# badge-inner-revA.net
KiCad netlist of a schematic drawn in EAGLE
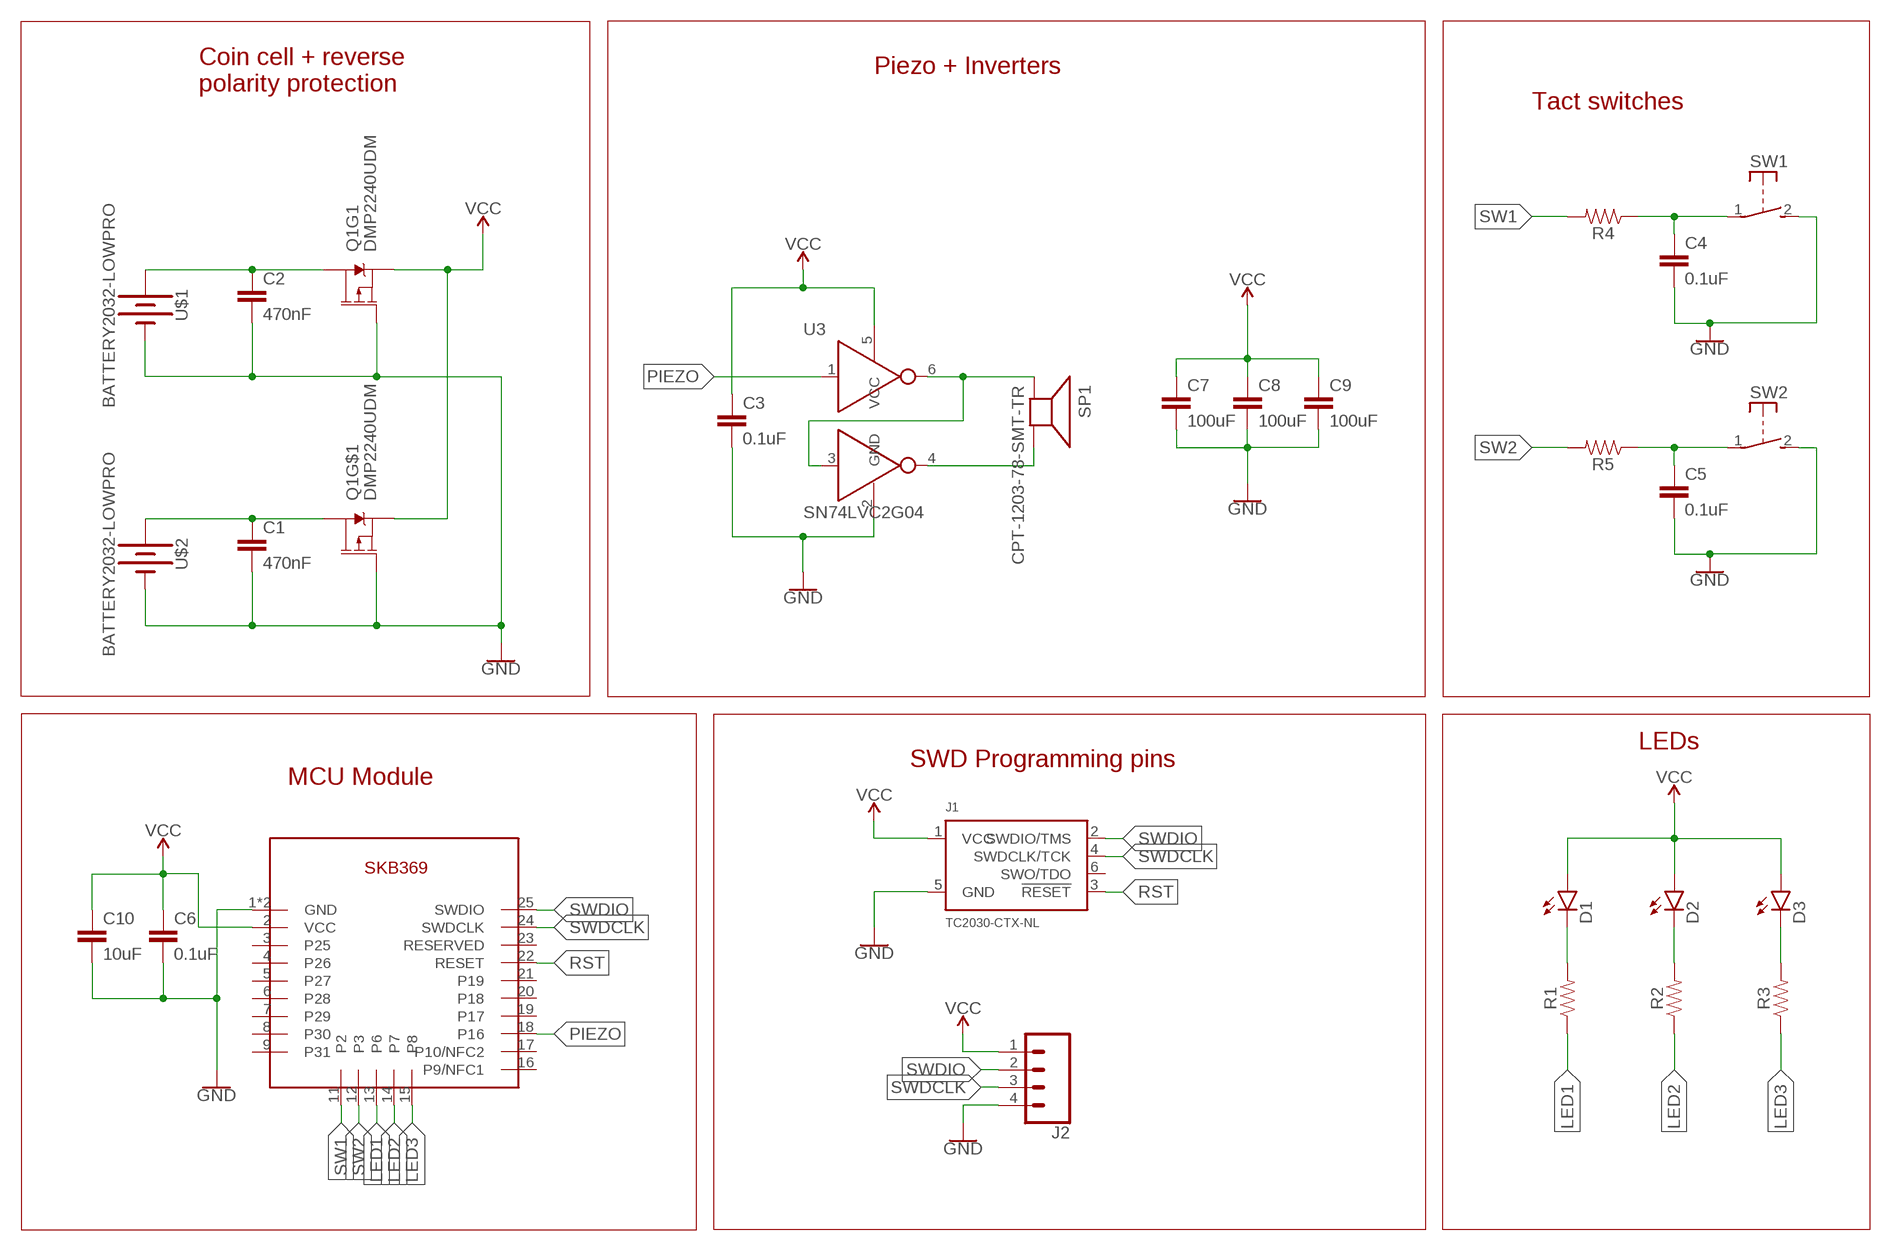
[diagram p0: schematic, sheet 1]

(export (version "E")
  (design (tool "Eeschema 10.0.6"))
  (components
    (comp (ref "C1")
      (value "470nF")
      (footprint "eagle-import:0603")
      (libsource (lib "eagle-import") (part "0.1UF-0603-25V-5%"))
    )
    (comp (ref "C2")
      (value "470nF")
      (footprint "eagle-import:0603")
      (libsource (lib "eagle-import") (part "0.1UF-0603-25V-5%"))
    )
    (comp (ref "C3")
      (value "0.1uF")
      (footprint "eagle-import:0603")
      (libsource (lib "eagle-import") (part "0.1UF-0603-25V-5%"))
    )
    (comp (ref "C4")
      (value "0.1uF")
      (footprint "eagle-import:0603")
      (libsource (lib "eagle-import") (part "0.1UF-0603-25V-5%"))
    )
    (comp (ref "C5")
      (value "0.1uF")
      (footprint "eagle-import:0603")
      (libsource (lib "eagle-import") (part "0.1UF-0603-25V-5%"))
    )
    (comp (ref "C6")
      (value "0.1uF")
      (footprint "eagle-import:0603")
      (libsource (lib "eagle-import") (part "0.1UF-0603-25V-5%"))
    )
    (comp (ref "C7")
      (value "100uF")
      (footprint "eagle-import:1206")
      (fields (field (name "SPICEPREFIX") "C"))
      (libsource (lib "eagle-import") (part "10UF-1206-6.3V-20%"))
    )
    (comp (ref "C8")
      (value "100uF")
      (footprint "eagle-import:1206")
      (fields (field (name "SPICEPREFIX") "C"))
      (libsource (lib "eagle-import") (part "10UF-1206-6.3V-20%"))
    )
    (comp (ref "C9")
      (value "100uF")
      (footprint "eagle-import:1206")
      (fields (field (name "SPICEPREFIX") "C"))
      (libsource (lib "eagle-import") (part "10UF-1206-6.3V-20%"))
    )
    (comp (ref "C10")
      (value "10uF")
      (footprint "eagle-import:0603")
      (libsource (lib "eagle-import") (part "0.1UF-0603-25V-5%"))
    )
    (comp (ref "D1")
      (value "SIDE-LED")
      (footprint "eagle-import:SIDE-LED")
      (libsource (lib "eagle-import") (part "SIDE-LED"))
    )
    (comp (ref "D2")
      (value "SIDE-LED")
      (footprint "eagle-import:SIDE-LED")
      (libsource (lib "eagle-import") (part "SIDE-LED"))
    )
    (comp (ref "D3")
      (value "SIDE-LED")
      (footprint "eagle-import:SIDE-LED")
      (libsource (lib "eagle-import") (part "SIDE-LED"))
    )
    (comp (ref "J1")
      (value "TC2030-CTX-NL")
      (footprint "eagle-import:TC2030-IDC-NL")
      (fields (field (name "MF") "Tag-Connect LLC") (field (name "MP") "TC2030-CTX"))
      (libsource (lib "eagle-import") (part "TC2030-CTX-NL"))
    )
    (comp (ref "J2")
      (value "CONN_04SMD_RA_FEMALE")
      (footprint "eagle-import:1X04_SMD_RA_FEMALE")
      (libsource (lib "eagle-import") (part "CONN_04SMD_RA_FEMALE"))
    )
    (comp (ref "Q1")
      (value "DMP2240UDM")
      (footprint "eagle-import:SOT26")
      (libsource (lib "eagle-import") (part "MOSFET_PCH_DUAL-DMP2240UDM"))
    )
    (comp (ref "R1")
      (value "0.05OHM-0603-1/5W-1%")
      (footprint "eagle-import:0603")
      (libsource (lib "eagle-import") (part "0.05OHM-0603-1/5W-1%"))
    )
    (comp (ref "R2")
      (value "0.05OHM-0603-1/5W-1%")
      (footprint "eagle-import:0603")
      (libsource (lib "eagle-import") (part "0.05OHM-0603-1/5W-1%"))
    )
    (comp (ref "R3")
      (value "0.05OHM-0603-1/5W-1%")
      (footprint "eagle-import:0603")
      (libsource (lib "eagle-import") (part "0.05OHM-0603-1/5W-1%"))
    )
    (comp (ref "R4")
      (value "0.05OHM-0603-1/5W-1%")
      (footprint "eagle-import:0603")
      (libsource (lib "eagle-import") (part "0.05OHM-0603-1/5W-1%"))
    )
    (comp (ref "R5")
      (value "0.05OHM-0603-1/5W-1%")
      (footprint "eagle-import:0603")
      (libsource (lib "eagle-import") (part "0.05OHM-0603-1/5W-1%"))
    )
    (comp (ref "SP1")
      (value "CPT-1203-78-SMT-TR")
      (footprint "eagle-import:CPT-1203-78-SMT-TR")
      (libsource (lib "eagle-import") (part "SPEAKER"))
    )
    (comp (ref "SW1")
      (value "EVQP4")
      (footprint "eagle-import:EVQP4KB")
      (libsource (lib "eagle-import") (part "EVQP4"))
    )
    (comp (ref "SW2")
      (value "EVQP4")
      (footprint "eagle-import:EVQP4KB")
      (libsource (lib "eagle-import") (part "EVQP4"))
    )
    (comp (ref "U$1")
      (value "BATTERY2032-LOWPRO")
      (footprint "eagle-import:COINCELL20LOWPRO")
      (libsource (lib "eagle-import") (part "BATTERY2032-LOWPRO"))
    )
    (comp (ref "U$2")
      (value "BATTERY2032-LOWPRO")
      (footprint "eagle-import:COINCELL20LOWPRO")
      (libsource (lib "eagle-import") (part "BATTERY2032-LOWPRO"))
    )
    (comp (ref "U1")
      (value "SKB369")
      (footprint "eagle-import:SKB369")
      (libsource (lib "eagle-import") (part "SKB369"))
    )
    (comp (ref "U3")
      (value "SN74LVC2G04")
      (footprint "eagle-import:SC70")
      (libsource (lib "eagle-import") (part "DUAL-INVERTERSN74LVC2G04"))
    )
  )
  (nets
    (net (code "1") (name "GND") (class "Default")
      (node (ref "C1") (pin "2") (pinfunction "2_2") (pintype "passive"))
      (node (ref "C10") (pin "2") (pinfunction "2_2") (pintype "passive"))
      (node (ref "C2") (pin "2") (pinfunction "2_2") (pintype "passive"))
      (node (ref "C3") (pin "2") (pinfunction "2_2") (pintype "passive"))
      (node (ref "C4") (pin "2") (pinfunction "2_2") (pintype "passive"))
      (node (ref "C5") (pin "2") (pinfunction "2_2") (pintype "passive"))
      (node (ref "C6") (pin "2") (pinfunction "2_2") (pintype "passive"))
      (node (ref "C7") (pin "2") (pinfunction "2_2") (pintype "passive"))
      (node (ref "C8") (pin "2") (pinfunction "2_2") (pintype "passive"))
      (node (ref "C9") (pin "2") (pinfunction "2_2") (pintype "passive"))
      (node (ref "J1") (pin "5") (pinfunction "GND_5") (pintype "bidirectional"))
      (node (ref "J2") (pin "4") (pinfunction "4_4") (pintype "passive"))
      (node (ref "Q1") (pin "G1") (pinfunction "G_G1") (pintype "bidirectional"))
      (node (ref "Q1") (pin "G2") (pinfunction "G_G2") (pintype "bidirectional"))
      (node (ref "SW1") (pin "2") (pinfunction "S_2") (pintype "passive"))
      (node (ref "SW2") (pin "2") (pinfunction "S_2") (pintype "passive"))
      (node (ref "U$1") (pin "P$2") (pinfunction "-_P$2") (pintype "power_in"))
      (node (ref "U$2") (pin "P$2") (pinfunction "-_P$2") (pintype "power_in"))
      (node (ref "U1") (pin "1") (pinfunction "GND_1") (pintype "bidirectional"))
      (node (ref "U1") (pin "10") (pinfunction "GND_10") (pintype "bidirectional"))
      (node (ref "U3") (pin "2") (pinfunction "GND_2") (pintype "bidirectional"))
    )
    (net (code "2") (name "LED1") (class "Default")
      (node (ref "R1") (pin "1") (pinfunction "1_1") (pintype "passive"))
      (node (ref "U1") (pin "13") (pinfunction "P6_13") (pintype "bidirectional"))
    )
    (net (code "3") (name "LED2") (class "Default")
      (node (ref "R2") (pin "1") (pinfunction "1_1") (pintype "passive"))
      (node (ref "U1") (pin "14") (pinfunction "P7_14") (pintype "bidirectional"))
    )
    (net (code "4") (name "LED3") (class "Default")
      (node (ref "R3") (pin "1") (pinfunction "1_1") (pintype "passive"))
      (node (ref "U1") (pin "15") (pinfunction "P8_15") (pintype "bidirectional"))
    )
    (net (code "5") (name "Net-(D1-C)") (class "Default")
      (node (ref "D1") (pin "1") (pinfunction "C_1") (pintype "passive"))
      (node (ref "R1") (pin "2") (pinfunction "2_2") (pintype "passive"))
    )
    (net (code "6") (name "Net-(D2-C)") (class "Default")
      (node (ref "D2") (pin "1") (pinfunction "C_1") (pintype "passive"))
      (node (ref "R2") (pin "2") (pinfunction "2_2") (pintype "passive"))
    )
    (net (code "7") (name "Net-(D3-C)") (class "Default")
      (node (ref "D3") (pin "1") (pinfunction "C_1") (pintype "passive"))
      (node (ref "R3") (pin "2") (pinfunction "2_2") (pintype "passive"))
    )
    (net (code "8") (name "Net-(Q1A-D)") (class "Default")
      (node (ref "C1") (pin "1") (pinfunction "1_1") (pintype "passive"))
      (node (ref "Q1") (pin "D2") (pinfunction "D_D2") (pintype "bidirectional"))
      (node (ref "U$2") (pin "P$1") (pinfunction "+_P$1") (pintype "power_in"))
    )
    (net (code "9") (name "Net-(Q1B-D)") (class "Default")
      (node (ref "C2") (pin "1") (pinfunction "1_1") (pintype "passive"))
      (node (ref "Q1") (pin "D1") (pinfunction "D_D1") (pintype "bidirectional"))
      (node (ref "U$1") (pin "P$1") (pinfunction "+_P$1") (pintype "power_in"))
    )
    (net (code "10") (name "Net-(SP1-+)") (class "Default")
      (node (ref "SP1") (pin "P$1") (pinfunction "+_P$1") (pintype "passive"))
      (node (ref "U3") (pin "3") (pinfunction "A2_3") (pintype "bidirectional"))
      (node (ref "U3") (pin "6") (pinfunction "Y1_6") (pintype "bidirectional"))
    )
    (net (code "11") (name "Net-(SP1--)") (class "Default")
      (node (ref "SP1") (pin "P$2") (pinfunction "-_P$2") (pintype "passive"))
      (node (ref "U3") (pin "4") (pinfunction "Y2_4") (pintype "bidirectional"))
    )
    (net (code "12") (name "Net-(SW1-P)") (class "Default")
      (node (ref "C4") (pin "1") (pinfunction "1_1") (pintype "passive"))
      (node (ref "R4") (pin "1") (pinfunction "1_1") (pintype "passive"))
      (node (ref "SW1") (pin "1") (pinfunction "P_1") (pintype "passive"))
    )
    (net (code "13") (name "Net-(SW2-P)") (class "Default")
      (node (ref "C5") (pin "1") (pinfunction "1_1") (pintype "passive"))
      (node (ref "R5") (pin "1") (pinfunction "1_1") (pintype "passive"))
      (node (ref "SW2") (pin "1") (pinfunction "P_1") (pintype "passive"))
    )
    (net (code "14") (name "PIEZO") (class "Default")
      (node (ref "U1") (pin "18") (pinfunction "P16_18") (pintype "bidirectional"))
      (node (ref "U3") (pin "1") (pinfunction "A1_1") (pintype "bidirectional"))
    )
    (net (code "15") (name "RST") (class "Default")
      (node (ref "J1") (pin "3") (pinfunction "~{RESET}_3") (pintype "bidirectional"))
      (node (ref "U1") (pin "22") (pinfunction "RESET_22") (pintype "bidirectional"))
    )
    (net (code "16") (name "SW1") (class "Default")
      (node (ref "R4") (pin "2") (pinfunction "2_2") (pintype "passive"))
      (node (ref "U1") (pin "11") (pinfunction "P2_11") (pintype "bidirectional"))
    )
    (net (code "17") (name "SW2") (class "Default")
      (node (ref "R5") (pin "2") (pinfunction "2_2") (pintype "passive"))
      (node (ref "U1") (pin "12") (pinfunction "P3_12") (pintype "bidirectional"))
    )
    (net (code "18") (name "SWDCLK") (class "Default")
      (node (ref "J1") (pin "4") (pinfunction "SWDCLK/TCK_4") (pintype "bidirectional"))
      (node (ref "J2") (pin "3") (pinfunction "3_3") (pintype "passive"))
      (node (ref "U1") (pin "24") (pinfunction "SWDCLK_24") (pintype "bidirectional"))
    )
    (net (code "19") (name "SWDIO") (class "Default")
      (node (ref "J1") (pin "2") (pinfunction "SWDIO/TMS_2") (pintype "bidirectional"))
      (node (ref "J2") (pin "2") (pinfunction "2_2") (pintype "passive"))
      (node (ref "U1") (pin "25") (pinfunction "SWDIO_25") (pintype "bidirectional"))
    )
    (net (code "20") (name "VCC") (class "Default")
      (node (ref "C10") (pin "1") (pinfunction "1_1") (pintype "passive"))
      (node (ref "C3") (pin "1") (pinfunction "1_1") (pintype "passive"))
      (node (ref "C6") (pin "1") (pinfunction "1_1") (pintype "passive"))
      (node (ref "C7") (pin "1") (pinfunction "1_1") (pintype "passive"))
      (node (ref "C8") (pin "1") (pinfunction "1_1") (pintype "passive"))
      (node (ref "C9") (pin "1") (pinfunction "1_1") (pintype "passive"))
      (node (ref "D1") (pin "2") (pinfunction "A_2") (pintype "passive"))
      (node (ref "D2") (pin "2") (pinfunction "A_2") (pintype "passive"))
      (node (ref "D3") (pin "2") (pinfunction "A_2") (pintype "passive"))
      (node (ref "J1") (pin "1") (pinfunction "VCC_1") (pintype "bidirectional"))
      (node (ref "J2") (pin "1") (pinfunction "1_1") (pintype "passive"))
      (node (ref "Q1") (pin "S1") (pinfunction "S_S1") (pintype "bidirectional"))
      (node (ref "Q1") (pin "S2") (pinfunction "S_S2") (pintype "bidirectional"))
      (node (ref "U1") (pin "2") (pinfunction "VCC_2") (pintype "bidirectional"))
      (node (ref "U3") (pin "5") (pinfunction "VCC_5") (pintype "bidirectional"))
    )
    (net (code "21") (name "unconnected-(J1-SWO{slash}TDO-Pad6)") (class "Default")
      (node (ref "J1") (pin "6") (pinfunction "SWO/TDO_6") (pintype "bidirectional"))
    )
    (net (code "22") (name "unconnected-(U1-P9{slash}NFC1-Pad16)") (class "Default")
      (node (ref "U1") (pin "16") (pinfunction "P9/NFC1_16") (pintype "bidirectional"))
    )
    (net (code "23") (name "unconnected-(U1-P10{slash}NFC2-Pad17)") (class "Default")
      (node (ref "U1") (pin "17") (pinfunction "P10/NFC2_17") (pintype "bidirectional"))
    )
    (net (code "24") (name "unconnected-(U1-P17-Pad19)") (class "Default")
      (node (ref "U1") (pin "19") (pinfunction "P17_19") (pintype "bidirectional"))
    )
    (net (code "25") (name "unconnected-(U1-P18-Pad20)") (class "Default")
      (node (ref "U1") (pin "20") (pinfunction "P18_20") (pintype "bidirectional"))
    )
    (net (code "26") (name "unconnected-(U1-P19-Pad21)") (class "Default")
      (node (ref "U1") (pin "21") (pinfunction "P19_21") (pintype "bidirectional"))
    )
    (net (code "27") (name "unconnected-(U1-P25-Pad3)") (class "Default")
      (node (ref "U1") (pin "3") (pinfunction "P25_3") (pintype "bidirectional"))
    )
    (net (code "28") (name "unconnected-(U1-P26-Pad4)") (class "Default")
      (node (ref "U1") (pin "4") (pinfunction "P26_4") (pintype "bidirectional"))
    )
    (net (code "29") (name "unconnected-(U1-P27-Pad5)") (class "Default")
      (node (ref "U1") (pin "5") (pinfunction "P27_5") (pintype "bidirectional"))
    )
    (net (code "30") (name "unconnected-(U1-P28-Pad6)") (class "Default")
      (node (ref "U1") (pin "6") (pinfunction "P28_6") (pintype "bidirectional"))
    )
    (net (code "31") (name "unconnected-(U1-P29-Pad7)") (class "Default")
      (node (ref "U1") (pin "7") (pinfunction "P29_7") (pintype "bidirectional"))
    )
    (net (code "32") (name "unconnected-(U1-P30-Pad8)") (class "Default")
      (node (ref "U1") (pin "8") (pinfunction "P30_8") (pintype "bidirectional"))
    )
    (net (code "33") (name "unconnected-(U1-P31-Pad9)") (class "Default")
      (node (ref "U1") (pin "9") (pinfunction "P31_9") (pintype "bidirectional"))
    )
    (net (code "34") (name "unconnected-(U1-RESERVED-Pad23)") (class "Default")
      (node (ref "U1") (pin "23") (pinfunction "RESERVED_23") (pintype "bidirectional"))
    )
  )
)
